# Model01_TOT.net
KiCad netlist of a schematic drawn in EAGLE
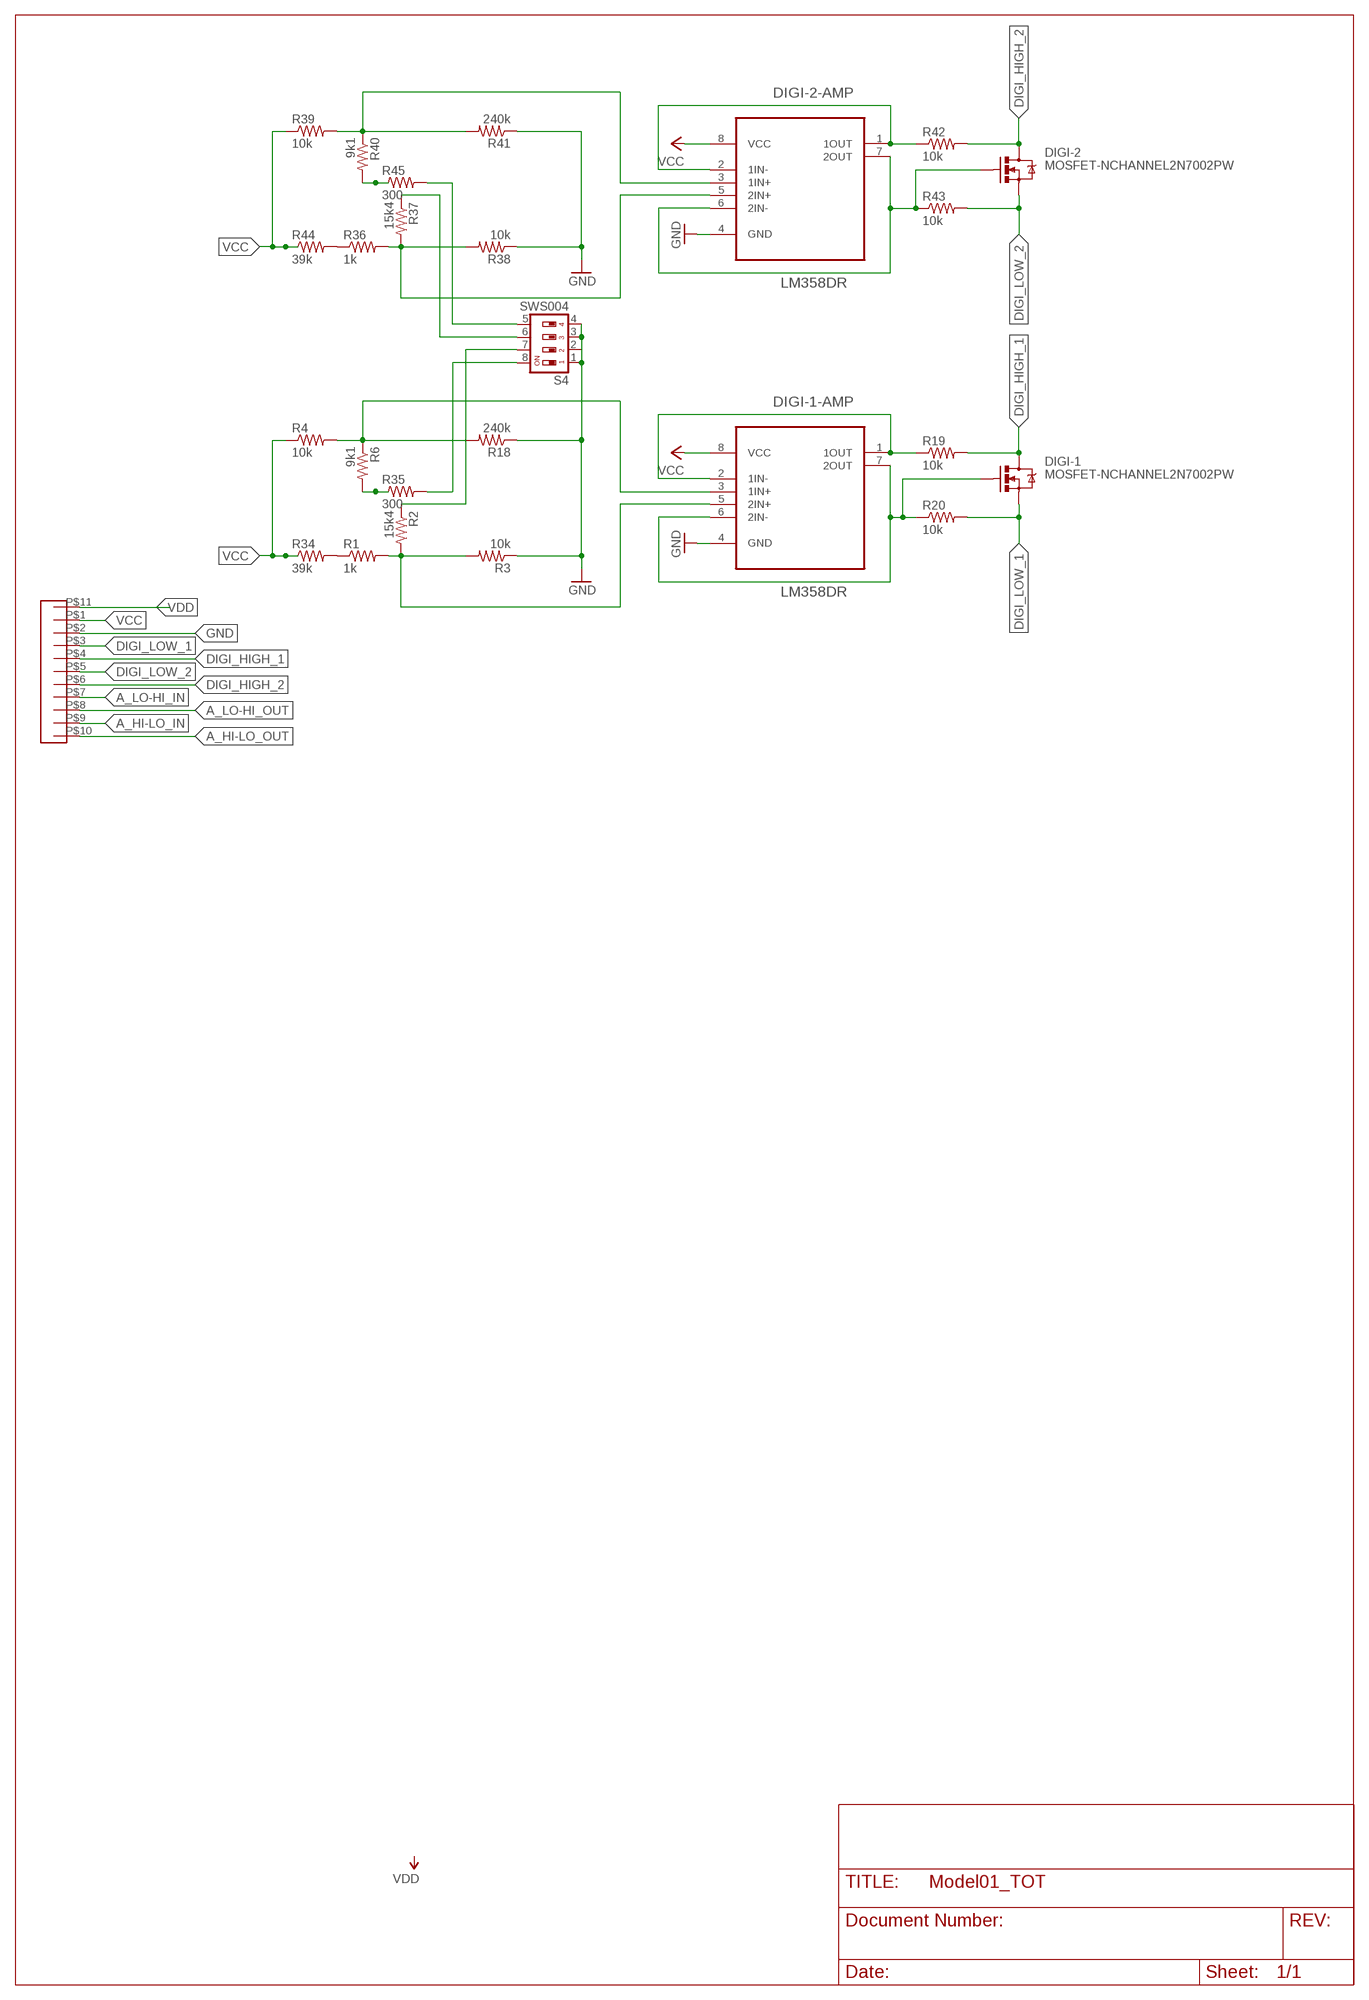
[diagram p0: schematic, sheet 1]

(export (version "E")
  (design (tool "Eeschema 10.0.6"))
  (components
    (comp (ref "DIGI-1")
      (value "MOSFET-NCHANNEL2N7002PW")
      (footprint "eagle-import:SOT323")
      (libsource (lib "eagle-import") (part "MOSFET-NCHANNEL2N7002PW"))
    )
    (comp (ref "DIGI-1-AMP")
      (value "LM358DR")
      (footprint "eagle-import:SOIC127P600X175-8N")
      (libsource (lib "eagle-import") (part "LM358DR"))
    )
    (comp (ref "DIGI-2")
      (value "MOSFET-NCHANNEL2N7002PW")
      (footprint "eagle-import:SOT323")
      (libsource (lib "eagle-import") (part "MOSFET-NCHANNEL2N7002PW"))
    )
    (comp (ref "DIGI-2-AMP")
      (value "LM358DR")
      (footprint "eagle-import:SOIC127P600X175-8N")
      (libsource (lib "eagle-import") (part "LM358DR"))
    )
    (comp (ref "R1")
      (value "1k")
      (footprint "eagle-import:R0805")
      (libsource (lib "eagle-import") (part "R-US_R0805"))
    )
    (comp (ref "R2")
      (value "15k4")
      (footprint "eagle-import:R0805")
      (libsource (lib "eagle-import") (part "R-US_R0805"))
    )
    (comp (ref "R3")
      (value "10k")
      (footprint "eagle-import:R0805")
      (libsource (lib "eagle-import") (part "R-US_R0805"))
    )
    (comp (ref "R4")
      (value "10k")
      (footprint "eagle-import:R0805")
      (libsource (lib "eagle-import") (part "R-US_R0805"))
    )
    (comp (ref "R6")
      (value "9k1")
      (footprint "eagle-import:R0805")
      (libsource (lib "eagle-import") (part "R-US_R0805"))
    )
    (comp (ref "R18")
      (value "240k")
      (footprint "eagle-import:R0805")
      (libsource (lib "eagle-import") (part "R-US_R0805"))
    )
    (comp (ref "R19")
      (value "10k")
      (footprint "eagle-import:R0805")
      (libsource (lib "eagle-import") (part "R-US_R0805"))
    )
    (comp (ref "R20")
      (value "10k")
      (footprint "eagle-import:R0805")
      (libsource (lib "eagle-import") (part "R-US_R0805"))
    )
    (comp (ref "R34")
      (value "39k")
      (footprint "eagle-import:R0805")
      (libsource (lib "eagle-import") (part "R-US_R0805"))
    )
    (comp (ref "R35")
      (value "300")
      (footprint "eagle-import:R0805")
      (libsource (lib "eagle-import") (part "R-US_R0805"))
    )
    (comp (ref "R36")
      (value "1k")
      (footprint "eagle-import:R0805")
      (libsource (lib "eagle-import") (part "R-US_R0805"))
    )
    (comp (ref "R37")
      (value "15k4")
      (footprint "eagle-import:R0805")
      (libsource (lib "eagle-import") (part "R-US_R0805"))
    )
    (comp (ref "R38")
      (value "10k")
      (footprint "eagle-import:R0805")
      (libsource (lib "eagle-import") (part "R-US_R0805"))
    )
    (comp (ref "R39")
      (value "10k")
      (footprint "eagle-import:R0805")
      (libsource (lib "eagle-import") (part "R-US_R0805"))
    )
    (comp (ref "R40")
      (value "9k1")
      (footprint "eagle-import:R0805")
      (libsource (lib "eagle-import") (part "R-US_R0805"))
    )
    (comp (ref "R41")
      (value "240k")
      (footprint "eagle-import:R0805")
      (libsource (lib "eagle-import") (part "R-US_R0805"))
    )
    (comp (ref "R42")
      (value "10k")
      (footprint "eagle-import:R0805")
      (libsource (lib "eagle-import") (part "R-US_R0805"))
    )
    (comp (ref "R43")
      (value "10k")
      (footprint "eagle-import:R0805")
      (libsource (lib "eagle-import") (part "R-US_R0805"))
    )
    (comp (ref "R44")
      (value "39k")
      (footprint "eagle-import:R0805")
      (libsource (lib "eagle-import") (part "R-US_R0805"))
    )
    (comp (ref "R45")
      (value "300")
      (footprint "eagle-import:R0805")
      (libsource (lib "eagle-import") (part "R-US_R0805"))
    )
    (comp (ref "S4")
      (value "SWS004")
      (footprint "eagle-import:SMS-004")
      (libsource (lib "eagle-import") (part "SWS004"))
    )
    (comp (ref "U$1")
      (value "5.08PITCHTERMINAL")
      (footprint "eagle-import:10KPL508")
      (libsource (lib "eagle-import") (part "5.08PITCHTERMINAL"))
    )
  )
  (nets
    (net (code "1") (name "A_HI-LO_IN") (class "Default")
      (node (ref "U$1") (pin "P$9") (pinfunction "P$9_P$9") (pintype "bidirectional"))
    )
    (net (code "2") (name "A_HI-LO_OUT") (class "Default")
      (node (ref "U$1") (pin "P$10") (pinfunction "P$10_P$10") (pintype "bidirectional"))
    )
    (net (code "3") (name "A_LO-HI_IN") (class "Default")
      (node (ref "U$1") (pin "P$7") (pinfunction "P$7_P$7") (pintype "bidirectional"))
    )
    (net (code "4") (name "A_LO-HI_OUT") (class "Default")
      (node (ref "U$1") (pin "P$8") (pinfunction "P$8_P$8") (pintype "bidirectional"))
    )
    (net (code "5") (name "DIGI_HIGH_1") (class "Default")
      (node (ref "DIGI-1") (pin "3") (pinfunction "D_3") (pintype "passive"))
      (node (ref "R19") (pin "2") (pinfunction "2_2") (pintype "passive"))
      (node (ref "U$1") (pin "P$4") (pinfunction "P$4_P$4") (pintype "bidirectional"))
    )
    (net (code "6") (name "DIGI_HIGH_2") (class "Default")
      (node (ref "DIGI-2") (pin "3") (pinfunction "D_3") (pintype "passive"))
      (node (ref "R42") (pin "2") (pinfunction "2_2") (pintype "passive"))
      (node (ref "U$1") (pin "P$6") (pinfunction "P$6_P$6") (pintype "bidirectional"))
    )
    (net (code "7") (name "DIGI_LOW_1") (class "Default")
      (node (ref "DIGI-1") (pin "2") (pinfunction "S_2") (pintype "passive"))
      (node (ref "R20") (pin "2") (pinfunction "2_2") (pintype "passive"))
      (node (ref "U$1") (pin "P$3") (pinfunction "P$3_P$3") (pintype "bidirectional"))
    )
    (net (code "8") (name "DIGI_LOW_2") (class "Default")
      (node (ref "DIGI-2") (pin "2") (pinfunction "S_2") (pintype "passive"))
      (node (ref "R43") (pin "2") (pinfunction "2_2") (pintype "passive"))
      (node (ref "U$1") (pin "P$5") (pinfunction "P$5_P$5") (pintype "bidirectional"))
    )
    (net (code "9") (name "GND") (class "Default")
      (node (ref "DIGI-1-AMP") (pin "4") (pinfunction "GND_4") (pintype "passive"))
      (node (ref "DIGI-2-AMP") (pin "4") (pinfunction "GND_4") (pintype "passive"))
      (node (ref "R18") (pin "1") (pinfunction "1_1") (pintype "passive"))
      (node (ref "R3") (pin "1") (pinfunction "1_1") (pintype "passive"))
      (node (ref "R38") (pin "1") (pinfunction "1_1") (pintype "passive"))
      (node (ref "R41") (pin "1") (pinfunction "1_1") (pintype "passive"))
      (node (ref "S4") (pin "1") (pinfunction "1_1") (pintype "passive"))
      (node (ref "S4") (pin "2") (pinfunction "2_2") (pintype "passive"))
      (node (ref "S4") (pin "3") (pinfunction "3_3") (pintype "passive"))
      (node (ref "S4") (pin "4") (pinfunction "4_4") (pintype "passive"))
      (node (ref "U$1") (pin "P$2") (pinfunction "P$2_P$2") (pintype "bidirectional"))
    )
    (net (code "10") (name "Net-(DIGI-1-AMP-1IN+)") (class "Default")
      (node (ref "DIGI-1-AMP") (pin "3") (pinfunction "1IN+_3") (pintype "input"))
      (node (ref "R18") (pin "2") (pinfunction "2_2") (pintype "passive"))
      (node (ref "R4") (pin "2") (pinfunction "2_2") (pintype "passive"))
      (node (ref "R6") (pin "1") (pinfunction "1_1") (pintype "passive"))
    )
    (net (code "11") (name "Net-(DIGI-1-AMP-1IN-)") (class "Default")
      (node (ref "DIGI-1-AMP") (pin "1") (pinfunction "1OUT_1") (pintype "output"))
      (node (ref "DIGI-1-AMP") (pin "2") (pinfunction "1IN-_2") (pintype "input"))
      (node (ref "R19") (pin "1") (pinfunction "1_1") (pintype "passive"))
    )
    (net (code "12") (name "Net-(DIGI-1-AMP-2IN+)") (class "Default")
      (node (ref "DIGI-1-AMP") (pin "5") (pinfunction "2IN+_5") (pintype "input"))
      (node (ref "R1") (pin "2") (pinfunction "2_2") (pintype "passive"))
      (node (ref "R2") (pin "2") (pinfunction "2_2") (pintype "passive"))
      (node (ref "R3") (pin "2") (pinfunction "2_2") (pintype "passive"))
    )
    (net (code "13") (name "Net-(DIGI-1-AMP-2IN-)") (class "Default")
      (node (ref "DIGI-1") (pin "1") (pinfunction "G_1") (pintype "passive"))
      (node (ref "DIGI-1-AMP") (pin "6") (pinfunction "2IN-_6") (pintype "input"))
      (node (ref "DIGI-1-AMP") (pin "7") (pinfunction "2OUT_7") (pintype "output"))
      (node (ref "R20") (pin "1") (pinfunction "1_1") (pintype "passive"))
    )
    (net (code "14") (name "Net-(DIGI-2-AMP-1IN+)") (class "Default")
      (node (ref "DIGI-2-AMP") (pin "3") (pinfunction "1IN+_3") (pintype "input"))
      (node (ref "R39") (pin "2") (pinfunction "2_2") (pintype "passive"))
      (node (ref "R40") (pin "1") (pinfunction "1_1") (pintype "passive"))
      (node (ref "R41") (pin "2") (pinfunction "2_2") (pintype "passive"))
    )
    (net (code "15") (name "Net-(DIGI-2-AMP-1IN-)") (class "Default")
      (node (ref "DIGI-2-AMP") (pin "1") (pinfunction "1OUT_1") (pintype "output"))
      (node (ref "DIGI-2-AMP") (pin "2") (pinfunction "1IN-_2") (pintype "input"))
      (node (ref "R42") (pin "1") (pinfunction "1_1") (pintype "passive"))
    )
    (net (code "16") (name "Net-(DIGI-2-AMP-2IN+)") (class "Default")
      (node (ref "DIGI-2-AMP") (pin "5") (pinfunction "2IN+_5") (pintype "input"))
      (node (ref "R36") (pin "2") (pinfunction "2_2") (pintype "passive"))
      (node (ref "R37") (pin "2") (pinfunction "2_2") (pintype "passive"))
      (node (ref "R38") (pin "2") (pinfunction "2_2") (pintype "passive"))
    )
    (net (code "17") (name "Net-(DIGI-2-AMP-2IN-)") (class "Default")
      (node (ref "DIGI-2") (pin "1") (pinfunction "G_1") (pintype "passive"))
      (node (ref "DIGI-2-AMP") (pin "6") (pinfunction "2IN-_6") (pintype "input"))
      (node (ref "DIGI-2-AMP") (pin "7") (pinfunction "2OUT_7") (pintype "output"))
      (node (ref "R43") (pin "1") (pinfunction "1_1") (pintype "passive"))
    )
    (net (code "18") (name "Net-(R1-Pad1)") (class "Default")
      (node (ref "R1") (pin "1") (pinfunction "1_1") (pintype "passive"))
      (node (ref "R34") (pin "2") (pinfunction "2_2") (pintype "passive"))
    )
    (net (code "19") (name "Net-(R2-Pad1)") (class "Default")
      (node (ref "R2") (pin "1") (pinfunction "1_1") (pintype "passive"))
      (node (ref "S4") (pin "7") (pinfunction "7_7") (pintype "passive"))
    )
    (net (code "20") (name "Net-(R35-Pad1)") (class "Default")
      (node (ref "R35") (pin "1") (pinfunction "1_1") (pintype "passive"))
      (node (ref "R6") (pin "2") (pinfunction "2_2") (pintype "passive"))
    )
    (net (code "21") (name "Net-(R35-Pad2)") (class "Default")
      (node (ref "R35") (pin "2") (pinfunction "2_2") (pintype "passive"))
      (node (ref "S4") (pin "8") (pinfunction "8_8") (pintype "passive"))
    )
    (net (code "22") (name "Net-(R36-Pad1)") (class "Default")
      (node (ref "R36") (pin "1") (pinfunction "1_1") (pintype "passive"))
      (node (ref "R44") (pin "2") (pinfunction "2_2") (pintype "passive"))
    )
    (net (code "23") (name "Net-(R37-Pad1)") (class "Default")
      (node (ref "R37") (pin "1") (pinfunction "1_1") (pintype "passive"))
      (node (ref "S4") (pin "6") (pinfunction "6_6") (pintype "passive"))
    )
    (net (code "24") (name "Net-(R40-Pad2)") (class "Default")
      (node (ref "R40") (pin "2") (pinfunction "2_2") (pintype "passive"))
      (node (ref "R45") (pin "1") (pinfunction "1_1") (pintype "passive"))
    )
    (net (code "25") (name "Net-(R45-Pad2)") (class "Default")
      (node (ref "R45") (pin "2") (pinfunction "2_2") (pintype "passive"))
      (node (ref "S4") (pin "5") (pinfunction "5_5") (pintype "passive"))
    )
    (net (code "26") (name "VCC") (class "Default")
      (node (ref "DIGI-1-AMP") (pin "8") (pinfunction "VCC_8") (pintype "power_in"))
      (node (ref "DIGI-2-AMP") (pin "8") (pinfunction "VCC_8") (pintype "power_in"))
      (node (ref "R34") (pin "1") (pinfunction "1_1") (pintype "passive"))
      (node (ref "R39") (pin "1") (pinfunction "1_1") (pintype "passive"))
      (node (ref "R4") (pin "1") (pinfunction "1_1") (pintype "passive"))
      (node (ref "R44") (pin "1") (pinfunction "1_1") (pintype "passive"))
      (node (ref "U$1") (pin "P$1") (pinfunction "P$1_P$1") (pintype "bidirectional"))
    )
    (net (code "27") (name "VDD") (class "Default")
      (node (ref "U$1") (pin "P$11") (pinfunction "P$11_P$11") (pintype "bidirectional"))
    )
  )
)
